# BreakoutPcb.net
KiCad netlist of a schematic drawn in Altium Designer
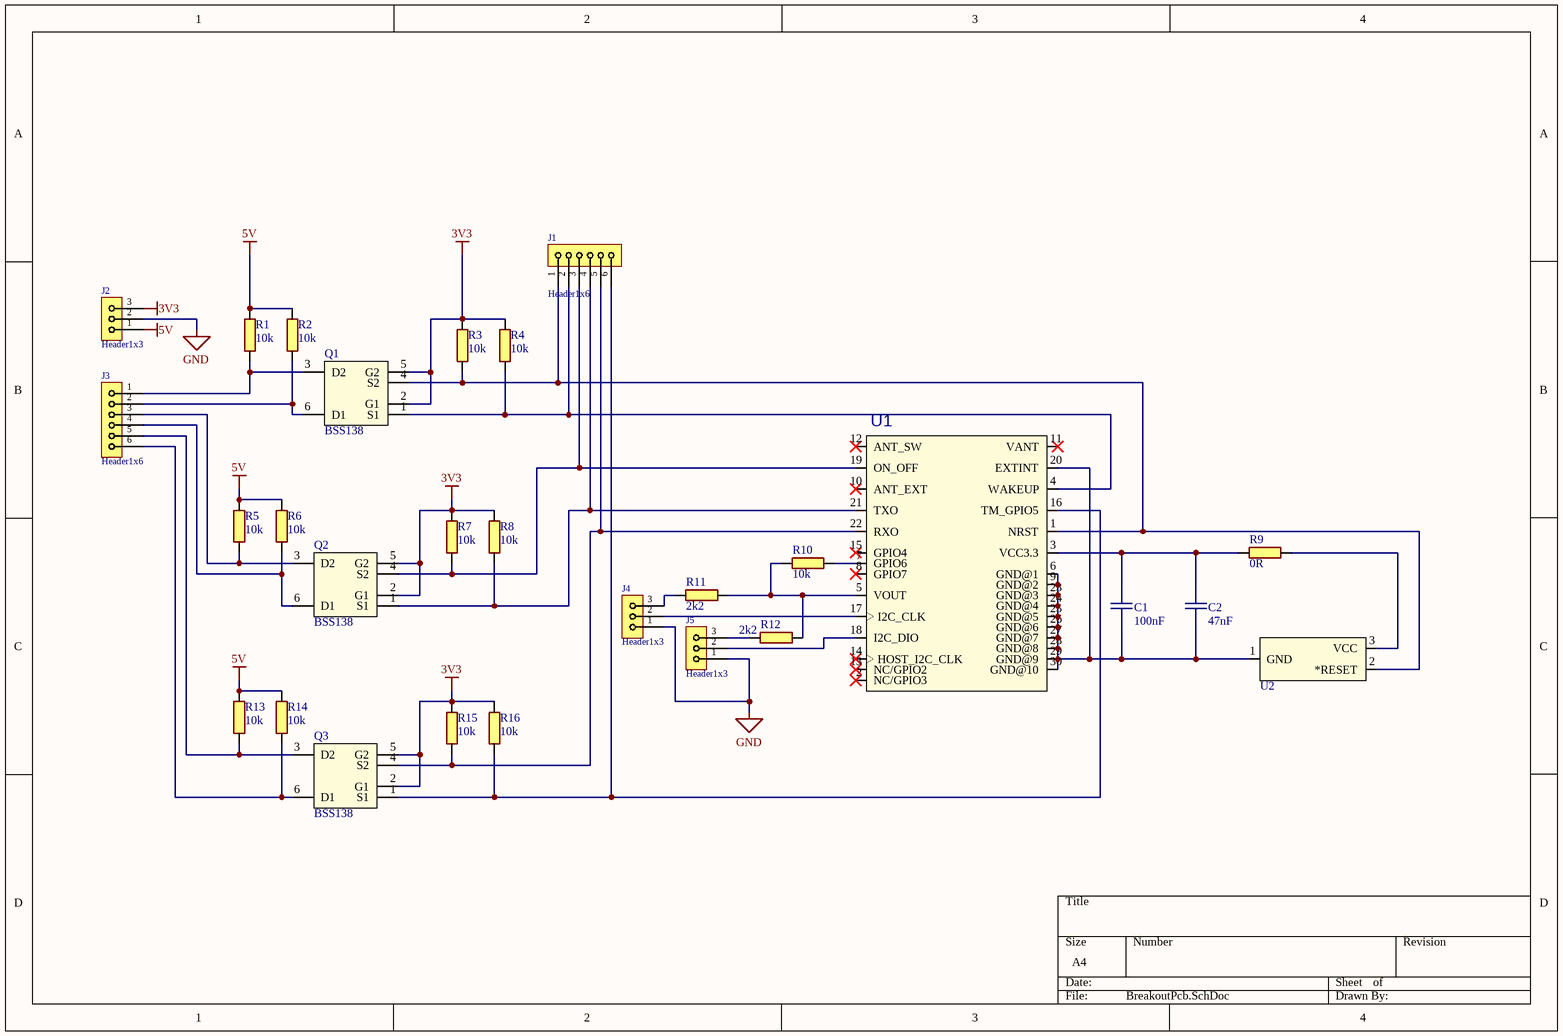
[diagram p0: BreakoutPcb.SchDoc]

(export (version "E")
  (design (tool "Eeschema 10.0.6"))
  (components
    (comp (ref "C1")
      (value "100nF")
      (footprint "CAPC0603(1608)55_N")
      (description "X7R 50V 5%")
      (libsource (lib "OVLib") (part "CAP"))
    )
    (comp (ref "C2")
      (value "47nF")
      (footprint "CAPC0805(2012)100_N")
      (description "X7R")
      (libsource (lib "OVLib") (part "CAP"))
    )
    (comp (ref "J1")
      (value "Header1x6")
      (footprint "HDRV6W64P254_1X6_1524X254X900B")
      (libsource (lib "OVLib") (part "Header1x6"))
    )
    (comp (ref "J2")
      (value "Header1x3")
      (footprint "HDRV3W64P254_1X3_762X254X900B")
      (libsource (lib "OVLib") (part "Header1x3"))
    )
    (comp (ref "J3")
      (value "Header1x6")
      (footprint "HDRV6W64P254_1X6_1524X254X900B")
      (libsource (lib "") (part "Header1x6_1"))
    )
    (comp (ref "J4")
      (value "Header1x3")
      (footprint "HDRV3W64P254_1X3_762X254X900B")
      (libsource (lib "OVLib") (part "Header1x3"))
    )
    (comp (ref "J5")
      (value "Header1x3")
      (footprint "HDRV3W64P254_1X3_762X254X900B")
      (libsource (lib "OVLib") (part "Header1x3"))
    )
    (comp (ref "Q1")
      (value "BSS138")
      (footprint "PCBComponent_1")
      (description "FET SM NCH 50V 220mA SOT23-3L")
      (libsource (lib "BSS138") (part "BSS138"))
    )
    (comp (ref "Q2")
      (value "BSS138")
      (footprint "PCBComponent_1")
      (description "FET SM NCH 50V 220mA SOT23-3L")
      (libsource (lib "BSS138") (part "BSS138"))
    )
    (comp (ref "Q3")
      (value "BSS138")
      (footprint "PCBComponent_1")
      (description "FET SM NCH 50V 220mA SOT23-3L")
      (libsource (lib "BSS138") (part "BSS138"))
    )
    (comp (ref "R1")
      (value "10k")
      (footprint "RESC0603(1608)_N")
      (description "0.1W 1% Thick film resistor")
      (libsource (lib "") (part "Resistor2_1"))
    )
    (comp (ref "R2")
      (value "10k")
      (footprint "RESC0603(1608)_N")
      (description "0.1W 1% Thick film resistor")
      (libsource (lib "") (part "Resistor2_1"))
    )
    (comp (ref "R3")
      (value "10k")
      (footprint "RESC0603(1608)_N")
      (description "0.1W 1% Thick film resistor")
      (libsource (lib "") (part "Resistor2_1"))
    )
    (comp (ref "R4")
      (value "10k")
      (footprint "RESC0603(1608)_N")
      (description "0.1W 1% Thick film resistor")
      (libsource (lib "") (part "Resistor2_1"))
    )
    (comp (ref "R5")
      (value "10k")
      (footprint "RESC0603(1608)_N")
      (description "0.1W 1% Thick film resistor")
      (libsource (lib "") (part "Resistor2_1"))
    )
    (comp (ref "R6")
      (value "10k")
      (footprint "RESC0603(1608)_N")
      (description "0.1W 1% Thick film resistor")
      (libsource (lib "") (part "Resistor2_1"))
    )
    (comp (ref "R7")
      (value "10k")
      (footprint "RESC0603(1608)_N")
      (description "0.1W 1% Thick film resistor")
      (libsource (lib "") (part "Resistor2_1"))
    )
    (comp (ref "R8")
      (value "10k")
      (footprint "RESC0603(1608)_N")
      (description "0.1W 1% Thick film resistor")
      (libsource (lib "") (part "Resistor2_1"))
    )
    (comp (ref "R9")
      (value "0R")
      (footprint "RESC0603(1608)_N")
      (description "0.1W 1% Thick film resistor")
      (libsource (lib "OVLib") (part "Resistor2"))
    )
    (comp (ref "R10")
      (value "10k")
      (footprint "RESC0603(1608)_N")
      (description "0.1W 1% Thick film resistor")
      (libsource (lib "OVLib") (part "Resistor2"))
    )
    (comp (ref "R11")
      (value "2k2")
      (footprint "RESC0603(1608)_N")
      (description "0.1W 1% Thick film resistor")
      (libsource (lib "OVLib") (part "Resistor2"))
    )
    (comp (ref "R12")
      (value "2k2")
      (footprint "RESC0603(1608)_N")
      (description "0.1W 1% Thick film resistor")
      (libsource (lib "OVLib") (part "Resistor2"))
    )
    (comp (ref "R13")
      (value "10k")
      (footprint "RESC0603(1608)_N")
      (description "0.1W 1% Thick film resistor")
      (libsource (lib "") (part "Resistor2_1"))
    )
    (comp (ref "R14")
      (value "10k")
      (footprint "RESC0603(1608)_N")
      (description "0.1W 1% Thick film resistor")
      (libsource (lib "") (part "Resistor2_1"))
    )
    (comp (ref "R15")
      (value "10k")
      (footprint "RESC0603(1608)_N")
      (description "0.1W 1% Thick film resistor")
      (libsource (lib "") (part "Resistor2_1"))
    )
    (comp (ref "R16")
      (value "10k")
      (footprint "RESC0603(1608)_N")
      (description "0.1W 1% Thick film resistor")
      (libsource (lib "") (part "Resistor2_1"))
    )
    (comp (ref "U1")
      (value "A2235-H")
      (footprint "XCVR_A2235-H")
      (description "Gps Module, Mini Outline w/ Ant")
      (fields (field (name "MF") "Maestro Wireless"))
      (libsource (lib "A2235-H") (part "A2235-H"))
    )
    (comp (ref "U2")
      (value "MAX809SEXR-T")
      (footprint "21-0075D")
      (description "PMIC - system monitor Maxim Integrated MAX809SEXR+T Reset/power-on reset SC 70 3")
      (fields (field (name "MP") "MAX809SEXR+T") (field (name "MF") "Maxim Integrated"))
      (libsource (lib "MAX809SEXR-T") (part "MAX809SEXR-T"))
    )
  )
  (nets
    (net (code "1") (name "3V3") (class "Default")
      (node (ref "J2") (pin "3") (pinfunction "3_3") (pintype "passive"))
      (node (ref "Q1") (pin "2") (pinfunction "G1_2") (pintype "passive"))
      (node (ref "Q1") (pin "5") (pinfunction "G2_5") (pintype "passive"))
      (node (ref "Q2") (pin "2") (pinfunction "G1_2") (pintype "passive"))
      (node (ref "Q2") (pin "5") (pinfunction "G2_5") (pintype "passive"))
      (node (ref "Q3") (pin "2") (pinfunction "G1_2") (pintype "passive"))
      (node (ref "Q3") (pin "5") (pinfunction "G2_5") (pintype "passive"))
      (node (ref "R15") (pin "2") (pinfunction "2_2") (pintype "passive"))
      (node (ref "R16") (pin "2") (pinfunction "2_2") (pintype "passive"))
      (node (ref "R3") (pin "2") (pinfunction "2_2") (pintype "passive"))
      (node (ref "R4") (pin "2") (pinfunction "2_2") (pintype "passive"))
      (node (ref "R7") (pin "2") (pinfunction "2_2") (pintype "passive"))
      (node (ref "R8") (pin "2") (pinfunction "2_2") (pintype "passive"))
    )
    (net (code "2") (name "5V") (class "Default")
      (node (ref "J2") (pin "1") (pinfunction "1_1") (pintype "passive"))
      (node (ref "R1") (pin "2") (pinfunction "2_2") (pintype "passive"))
      (node (ref "R13") (pin "2") (pinfunction "2_2") (pintype "passive"))
      (node (ref "R14") (pin "2") (pinfunction "2_2") (pintype "passive"))
      (node (ref "R2") (pin "2") (pinfunction "2_2") (pintype "passive"))
      (node (ref "R5") (pin "2") (pinfunction "2_2") (pintype "passive"))
      (node (ref "R6") (pin "2") (pinfunction "2_2") (pintype "passive"))
    )
    (net (code "3") (name "GND") (class "Default")
      (node (ref "J2") (pin "2") (pinfunction "2_2") (pintype "passive"))
      (node (ref "J4") (pin "1") (pinfunction "1_1") (pintype "passive"))
      (node (ref "J5") (pin "1") (pinfunction "1_1") (pintype "passive"))
    )
    (net (code "4") (name "Net-(J4-Pad3)") (class "Default")
      (node (ref "J4") (pin "3") (pinfunction "3_3") (pintype "passive"))
      (node (ref "R11") (pin "1") (pinfunction "1_1") (pintype "passive"))
    )
    (net (code "5") (name "Net-(J5-Pad3)") (class "Default")
      (node (ref "J5") (pin "3") (pinfunction "3_3") (pintype "passive"))
      (node (ref "R12") (pin "1") (pinfunction "1_1") (pintype "passive"))
    )
    (net (code "6") (name "Net-(Q1-D1)") (class "Default")
      (node (ref "J3") (pin "2") (pinfunction "2_2") (pintype "passive"))
      (node (ref "Q1") (pin "6") (pinfunction "D1_6") (pintype "passive"))
      (node (ref "R2") (pin "1") (pinfunction "1_1") (pintype "passive"))
    )
    (net (code "7") (name "Net-(Q1-D2)") (class "Default")
      (node (ref "J3") (pin "1") (pinfunction "1_1") (pintype "passive"))
      (node (ref "Q1") (pin "3") (pinfunction "D2_3") (pintype "passive"))
      (node (ref "R1") (pin "1") (pinfunction "1_1") (pintype "passive"))
    )
    (net (code "8") (name "Net-(Q1-S1)") (class "Default")
      (node (ref "J1") (pin "2") (pinfunction "2_2") (pintype "passive"))
      (node (ref "Q1") (pin "1") (pinfunction "S1_1") (pintype "passive"))
      (node (ref "R4") (pin "1") (pinfunction "1_1") (pintype "passive"))
      (node (ref "U1") (pin "4") (pinfunction "WAKEUP_4") (pintype "output"))
    )
    (net (code "9") (name "Net-(Q1-S2)") (class "Default")
      (node (ref "J1") (pin "1") (pinfunction "1_1") (pintype "passive"))
      (node (ref "Q1") (pin "4") (pinfunction "S2_4") (pintype "passive"))
      (node (ref "R3") (pin "1") (pinfunction "1_1") (pintype "passive"))
      (node (ref "U1") (pin "1") (pinfunction "NRST_1") (pintype "input"))
      (node (ref "U2") (pin "2") (pinfunction "*RESET_2") (pintype "output"))
    )
    (net (code "10") (name "Net-(Q2-D1)") (class "Default")
      (node (ref "J3") (pin "4") (pinfunction "4_4") (pintype "passive"))
      (node (ref "Q2") (pin "6") (pinfunction "D1_6") (pintype "passive"))
      (node (ref "R6") (pin "1") (pinfunction "1_1") (pintype "passive"))
    )
    (net (code "11") (name "Net-(Q2-D2)") (class "Default")
      (node (ref "J3") (pin "3") (pinfunction "3_3") (pintype "passive"))
      (node (ref "Q2") (pin "3") (pinfunction "D2_3") (pintype "passive"))
      (node (ref "R5") (pin "1") (pinfunction "1_1") (pintype "passive"))
    )
    (net (code "12") (name "Net-(Q2-S1)") (class "Default")
      (node (ref "J1") (pin "4") (pinfunction "4_4") (pintype "passive"))
      (node (ref "Q2") (pin "1") (pinfunction "S1_1") (pintype "passive"))
      (node (ref "R8") (pin "1") (pinfunction "1_1") (pintype "passive"))
      (node (ref "U1") (pin "21") (pinfunction "TXO_21") (pintype "output"))
    )
    (net (code "13") (name "Net-(Q2-S2)") (class "Default")
      (node (ref "J1") (pin "3") (pinfunction "3_3") (pintype "passive"))
      (node (ref "Q2") (pin "4") (pinfunction "S2_4") (pintype "passive"))
      (node (ref "R7") (pin "1") (pinfunction "1_1") (pintype "passive"))
      (node (ref "U1") (pin "19") (pinfunction "ON_OFF_19") (pintype "input"))
    )
    (net (code "14") (name "Net-(Q3-D1)") (class "Default")
      (node (ref "J3") (pin "6") (pinfunction "6_6") (pintype "passive"))
      (node (ref "Q3") (pin "6") (pinfunction "D1_6") (pintype "passive"))
      (node (ref "R14") (pin "1") (pinfunction "1_1") (pintype "passive"))
    )
    (net (code "15") (name "Net-(Q3-D2)") (class "Default")
      (node (ref "J3") (pin "5") (pinfunction "5_5") (pintype "passive"))
      (node (ref "Q3") (pin "3") (pinfunction "D2_3") (pintype "passive"))
      (node (ref "R13") (pin "1") (pinfunction "1_1") (pintype "passive"))
    )
    (net (code "16") (name "Net-(Q3-S1)") (class "Default")
      (node (ref "J1") (pin "6") (pinfunction "6_6") (pintype "passive"))
      (node (ref "Q3") (pin "1") (pinfunction "S1_1") (pintype "passive"))
      (node (ref "R16") (pin "1") (pinfunction "1_1") (pintype "passive"))
      (node (ref "U1") (pin "16") (pinfunction "TM_GPIO5_16") (pintype "output"))
    )
    (net (code "17") (name "Net-(Q3-S2)") (class "Default")
      (node (ref "J1") (pin "5") (pinfunction "5_5") (pintype "passive"))
      (node (ref "Q3") (pin "4") (pinfunction "S2_4") (pintype "passive"))
      (node (ref "R15") (pin "1") (pinfunction "1_1") (pintype "passive"))
      (node (ref "U1") (pin "22") (pinfunction "RXO_22") (pintype "input"))
    )
    (net (code "18") (name "Net-(U1-EXTINT)") (class "Default")
      (node (ref "C1") (pin "1") (pinfunction "1_1") (pintype "passive"))
      (node (ref "C2") (pin "1") (pinfunction "1_1") (pintype "passive"))
      (node (ref "U1") (pin "20") (pinfunction "EXTINT_20") (pintype "input"))
      (node (ref "U1") (pin "23") (pinfunction "GND@3_23") (pintype "power_in"))
      (node (ref "U1") (pin "24") (pinfunction "GND@4_24") (pintype "power_in"))
      (node (ref "U1") (pin "25") (pinfunction "GND@5_25") (pintype "power_in"))
      (node (ref "U1") (pin "26") (pinfunction "GND@6_26") (pintype "power_in"))
      (node (ref "U1") (pin "27") (pinfunction "GND@7_27") (pintype "power_in"))
      (node (ref "U1") (pin "28") (pinfunction "GND@8_28") (pintype "power_in"))
      (node (ref "U1") (pin "29") (pinfunction "GND@9_29") (pintype "power_in"))
      (node (ref "U1") (pin "30") (pinfunction "GND@10_30") (pintype "power_in"))
      (node (ref "U1") (pin "6") (pinfunction "GND@1_6") (pintype "power_in"))
      (node (ref "U1") (pin "9") (pinfunction "GND@2_9") (pintype "power_in"))
      (node (ref "U2") (pin "1") (pinfunction "GND_1") (pintype "power_in"))
    )
    (net (code "19") (name "Net-(U1-GPIO6)") (class "Default")
      (node (ref "R10") (pin "2") (pinfunction "2_2") (pintype "passive"))
      (node (ref "U1") (pin "7") (pinfunction "GPIO6_7") (pintype "input"))
    )
    (net (code "20") (name "Net-(U1-I2C_CLK)") (class "Default")
      (node (ref "J4") (pin "2") (pinfunction "2_2") (pintype "passive"))
      (node (ref "U1") (pin "17") (pinfunction "I2C_CLK_17") (pintype "bidirectional"))
    )
    (net (code "21") (name "Net-(U1-I2C_DIO)") (class "Default")
      (node (ref "J5") (pin "2") (pinfunction "2_2") (pintype "passive"))
      (node (ref "U1") (pin "18") (pinfunction "I2C_DIO_18") (pintype "bidirectional"))
    )
    (net (code "22") (name "Net-(U1-VCC3.3)") (class "Default")
      (node (ref "C1") (pin "2") (pinfunction "2_2") (pintype "passive"))
      (node (ref "C2") (pin "2") (pinfunction "2_2") (pintype "passive"))
      (node (ref "R9") (pin "1") (pinfunction "1_1") (pintype "passive"))
      (node (ref "U1") (pin "3") (pinfunction "VCC3.3_3") (pintype "power_in"))
    )
    (net (code "23") (name "Net-(U1-VOUT)") (class "Default")
      (node (ref "R10") (pin "1") (pinfunction "1_1") (pintype "passive"))
      (node (ref "R11") (pin "2") (pinfunction "2_2") (pintype "passive"))
      (node (ref "R12") (pin "2") (pinfunction "2_2") (pintype "passive"))
      (node (ref "U1") (pin "5") (pinfunction "VOUT_5") (pintype "output"))
    )
    (net (code "24") (name "Net-(U2-VCC)") (class "Default")
      (node (ref "R9") (pin "2") (pinfunction "2_2") (pintype "passive"))
      (node (ref "U2") (pin "3") (pinfunction "VCC_3") (pintype "power_in"))
    )
    (net (code "25") (name "unconnected-(U1-ANT_EXT-Pad10)") (class "Default")
      (node (ref "U1") (pin "10") (pinfunction "ANT_EXT_10") (pintype "input+no_connect"))
    )
    (net (code "26") (name "unconnected-(U1-ANT_SW-Pad12)") (class "Default")
      (node (ref "U1") (pin "12") (pinfunction "ANT_SW_12") (pintype "input+no_connect"))
    )
    (net (code "27") (name "unconnected-(U1-GPIO4-Pad15)") (class "Default")
      (node (ref "U1") (pin "15") (pinfunction "GPIO4_15") (pintype "input+no_connect"))
    )
    (net (code "28") (name "unconnected-(U1-GPIO7-Pad8)") (class "Default")
      (node (ref "U1") (pin "8") (pinfunction "GPIO7_8") (pintype "input+no_connect"))
    )
    (net (code "29") (name "unconnected-(U1-HOST_I2C_CLK-Pad14)") (class "Default")
      (node (ref "U1") (pin "14") (pinfunction "HOST_I2C_CLK_14") (pintype "bidirectional+no_connect"))
    )
    (net (code "30") (name "unconnected-(U1-NC{slash}GPIO2-Pad13)") (class "Default")
      (node (ref "U1") (pin "13") (pinfunction "NC/GPIO2_13") (pintype "bidirectional+no_connect"))
    )
    (net (code "31") (name "unconnected-(U1-NC{slash}GPIO3-Pad2)") (class "Default")
      (node (ref "U1") (pin "2") (pinfunction "NC/GPIO3_2") (pintype "bidirectional+no_connect"))
    )
    (net (code "32") (name "unconnected-(U1-VANT-Pad11)") (class "Default")
      (node (ref "U1") (pin "11") (pinfunction "VANT_11") (pintype "power_in+no_connect"))
    )
  )
)
